# interlinkP1A.net
KiCad netlist of a schematic drawn in Altium Designer
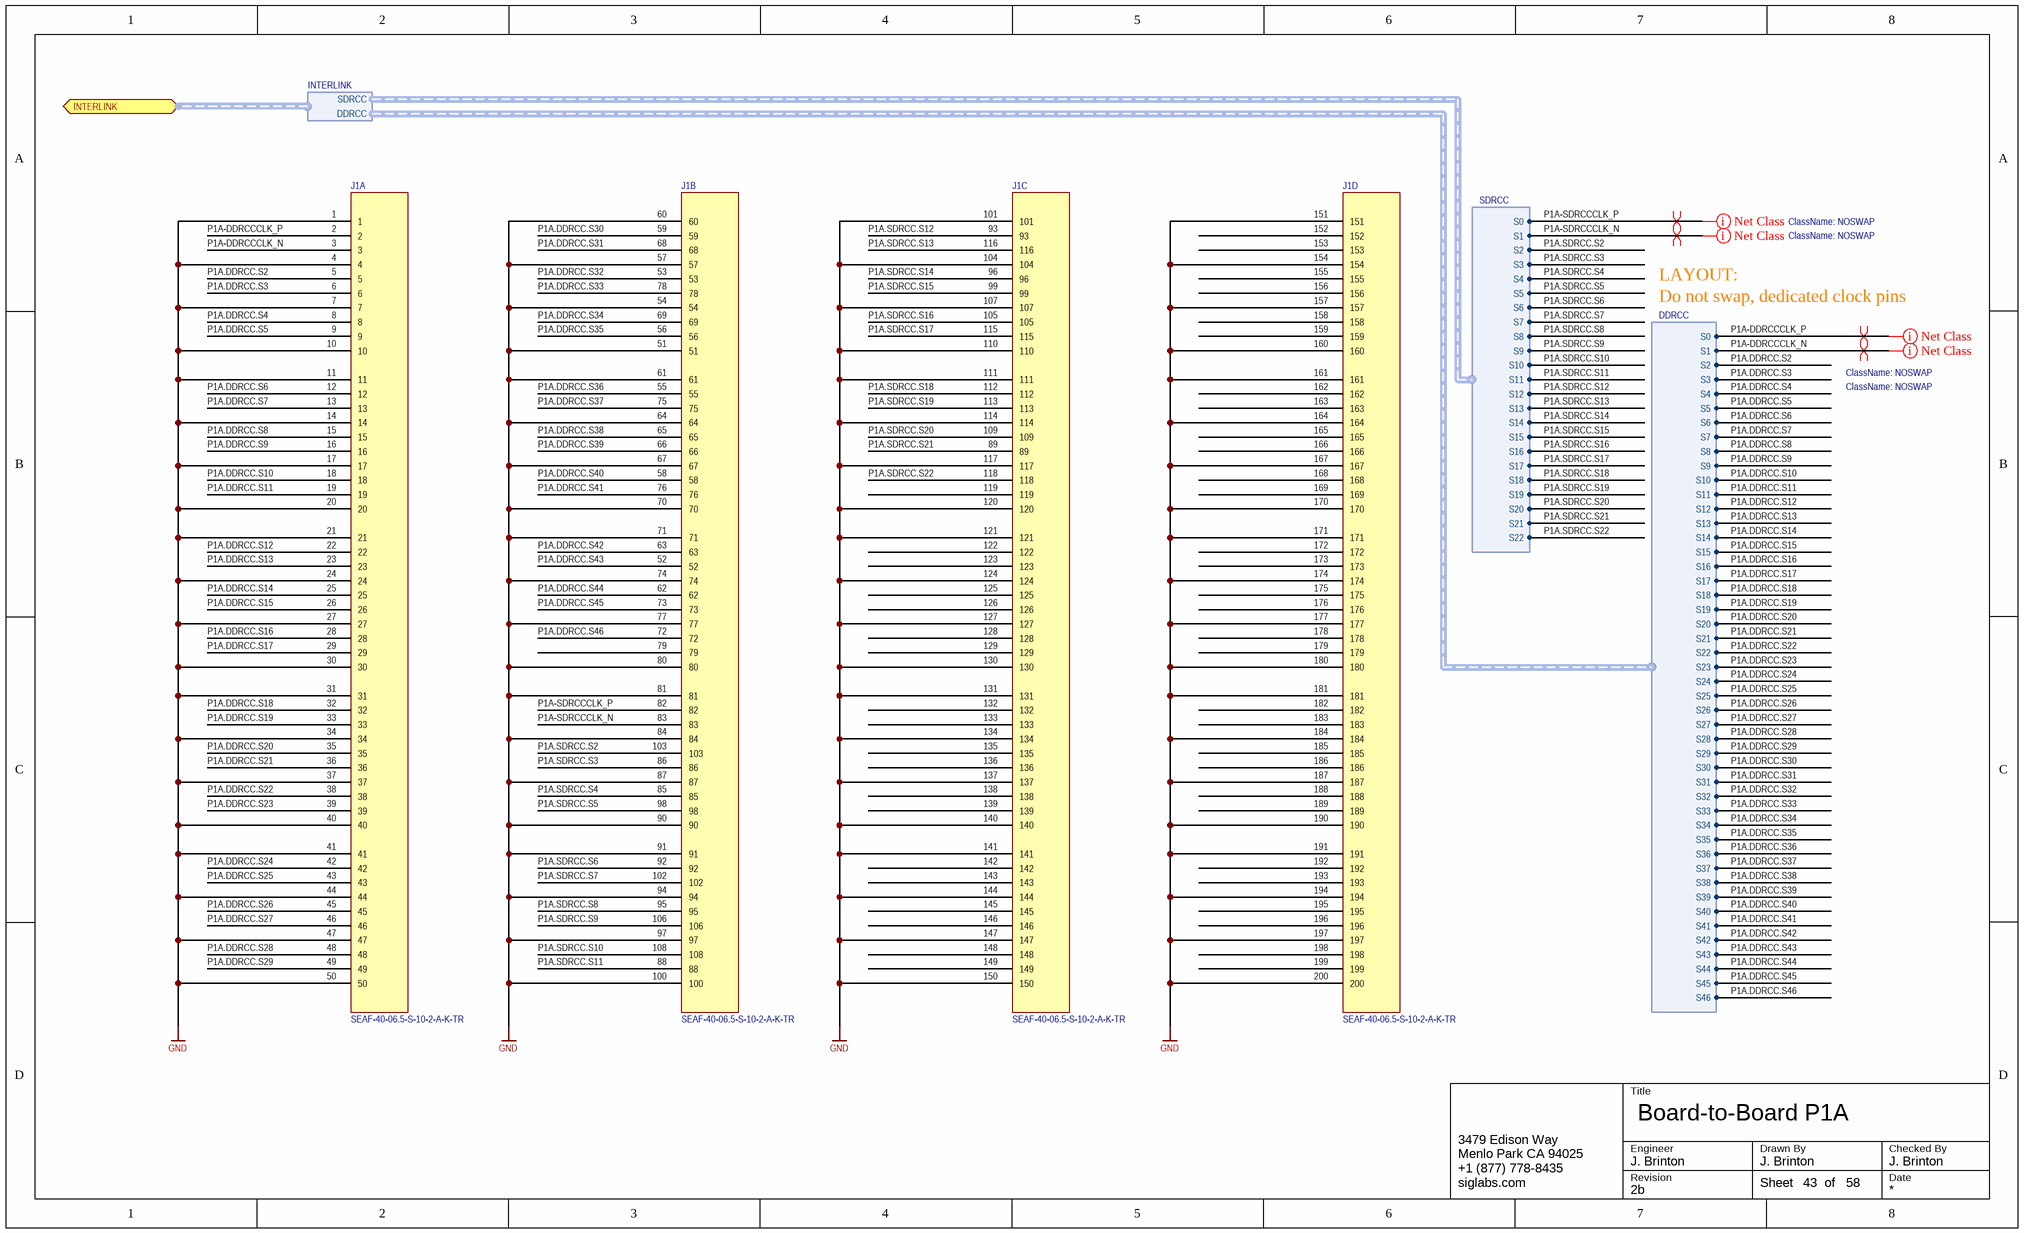
[diagram p0: interlinkP1A.SchDoc]

(export (version "E")
  (design (tool "Eeschema 10.0.6"))
  (components
    (comp (ref "J1")
      (value "SEAF-40-06.5-S-10-2-A-K-TR")
      (footprint "samtec:SEAF-40-06.5-S-10-2-A-K-TR")
      (description "Terminal Array Assembly, Surface Mount, 0.050\" Pitch, 400 Pins")
      (fields (field (name "MANUFACTURER") "Samtec"))
      (libsource (lib "") (part "SEAF-40-06.5-S-10-2-A-K-TR_2"))
    )
  )
  (nets
    (net (code "4") (name "/P1A-DDRCCCLK_N") (class "Default")
      (node (ref "J1") (pin "3") (pinfunction "3_3") (pintype "passive"))
    )
    (net (code "5") (name "/P1A-DDRCCCLK_P") (class "Default")
      (node (ref "J1") (pin "2") (pinfunction "2_2") (pintype "passive"))
    )
    (net (code "6") (name "/P1A-SDRCCCLK_N") (class "Default")
      (node (ref "J1") (pin "83") (pinfunction "83_83") (pintype "passive"))
    )
    (net (code "7") (name "/P1A-SDRCCCLK_P") (class "Default")
      (node (ref "J1") (pin "82") (pinfunction "82_82") (pintype "passive"))
    )
    (net (code "8") (name "/P1A.DDRCC.S2") (class "Default")
      (node (ref "J1") (pin "5") (pinfunction "5_5") (pintype "passive"))
    )
    (net (code "9") (name "/P1A.DDRCC.S3") (class "Default")
      (node (ref "J1") (pin "6") (pinfunction "6_6") (pintype "passive"))
    )
    (net (code "10") (name "/P1A.DDRCC.S4") (class "Default")
      (node (ref "J1") (pin "8") (pinfunction "8_8") (pintype "passive"))
    )
    (net (code "11") (name "/P1A.DDRCC.S5") (class "Default")
      (node (ref "J1") (pin "9") (pinfunction "9_9") (pintype "passive"))
    )
    (net (code "12") (name "/P1A.DDRCC.S6") (class "Default")
      (node (ref "J1") (pin "12") (pinfunction "12_12") (pintype "passive"))
    )
    (net (code "13") (name "/P1A.DDRCC.S7") (class "Default")
      (node (ref "J1") (pin "13") (pinfunction "13_13") (pintype "passive"))
    )
    (net (code "14") (name "/P1A.DDRCC.S8") (class "Default")
      (node (ref "J1") (pin "15") (pinfunction "15_15") (pintype "passive"))
    )
    (net (code "15") (name "/P1A.DDRCC.S9") (class "Default")
      (node (ref "J1") (pin "16") (pinfunction "16_16") (pintype "passive"))
    )
    (net (code "16") (name "/P1A.DDRCC.S10") (class "Default")
      (node (ref "J1") (pin "18") (pinfunction "18_18") (pintype "passive"))
    )
    (net (code "17") (name "/P1A.DDRCC.S11") (class "Default")
      (node (ref "J1") (pin "19") (pinfunction "19_19") (pintype "passive"))
    )
    (net (code "18") (name "/P1A.DDRCC.S12") (class "Default")
      (node (ref "J1") (pin "22") (pinfunction "22_22") (pintype "passive"))
    )
    (net (code "19") (name "/P1A.DDRCC.S13") (class "Default")
      (node (ref "J1") (pin "23") (pinfunction "23_23") (pintype "passive"))
    )
    (net (code "20") (name "/P1A.DDRCC.S14") (class "Default")
      (node (ref "J1") (pin "25") (pinfunction "25_25") (pintype "passive"))
    )
    (net (code "21") (name "/P1A.DDRCC.S15") (class "Default")
      (node (ref "J1") (pin "26") (pinfunction "26_26") (pintype "passive"))
    )
    (net (code "22") (name "/P1A.DDRCC.S16") (class "Default")
      (node (ref "J1") (pin "28") (pinfunction "28_28") (pintype "passive"))
    )
    (net (code "23") (name "/P1A.DDRCC.S17") (class "Default")
      (node (ref "J1") (pin "29") (pinfunction "29_29") (pintype "passive"))
    )
    (net (code "24") (name "/P1A.DDRCC.S18") (class "Default")
      (node (ref "J1") (pin "32") (pinfunction "32_32") (pintype "passive"))
    )
    (net (code "25") (name "/P1A.DDRCC.S19") (class "Default")
      (node (ref "J1") (pin "33") (pinfunction "33_33") (pintype "passive"))
    )
    (net (code "26") (name "/P1A.DDRCC.S20") (class "Default")
      (node (ref "J1") (pin "35") (pinfunction "35_35") (pintype "passive"))
    )
    (net (code "27") (name "/P1A.DDRCC.S21") (class "Default")
      (node (ref "J1") (pin "36") (pinfunction "36_36") (pintype "passive"))
    )
    (net (code "28") (name "/P1A.DDRCC.S22") (class "Default")
      (node (ref "J1") (pin "38") (pinfunction "38_38") (pintype "passive"))
    )
    (net (code "29") (name "/P1A.DDRCC.S23") (class "Default")
      (node (ref "J1") (pin "39") (pinfunction "39_39") (pintype "passive"))
    )
    (net (code "30") (name "/P1A.DDRCC.S24") (class "Default")
      (node (ref "J1") (pin "42") (pinfunction "42_42") (pintype "passive"))
    )
    (net (code "31") (name "/P1A.DDRCC.S25") (class "Default")
      (node (ref "J1") (pin "43") (pinfunction "43_43") (pintype "passive"))
    )
    (net (code "32") (name "/P1A.DDRCC.S26") (class "Default")
      (node (ref "J1") (pin "45") (pinfunction "45_45") (pintype "passive"))
    )
    (net (code "33") (name "/P1A.DDRCC.S27") (class "Default")
      (node (ref "J1") (pin "46") (pinfunction "46_46") (pintype "passive"))
    )
    (net (code "34") (name "/P1A.DDRCC.S28") (class "Default")
      (node (ref "J1") (pin "48") (pinfunction "48_48") (pintype "passive"))
    )
    (net (code "35") (name "/P1A.DDRCC.S29") (class "Default")
      (node (ref "J1") (pin "49") (pinfunction "49_49") (pintype "passive"))
    )
    (net (code "36") (name "/P1A.DDRCC.S30") (class "Default")
      (node (ref "J1") (pin "59") (pinfunction "59_59") (pintype "passive"))
    )
    (net (code "37") (name "/P1A.DDRCC.S31") (class "Default")
      (node (ref "J1") (pin "68") (pinfunction "68_68") (pintype "passive"))
    )
    (net (code "38") (name "/P1A.DDRCC.S32") (class "Default")
      (node (ref "J1") (pin "53") (pinfunction "53_53") (pintype "passive"))
    )
    (net (code "39") (name "/P1A.DDRCC.S33") (class "Default")
      (node (ref "J1") (pin "78") (pinfunction "78_78") (pintype "passive"))
    )
    (net (code "40") (name "/P1A.DDRCC.S34") (class "Default")
      (node (ref "J1") (pin "69") (pinfunction "69_69") (pintype "passive"))
    )
    (net (code "41") (name "/P1A.DDRCC.S35") (class "Default")
      (node (ref "J1") (pin "56") (pinfunction "56_56") (pintype "passive"))
    )
    (net (code "42") (name "/P1A.DDRCC.S36") (class "Default")
      (node (ref "J1") (pin "55") (pinfunction "55_55") (pintype "passive"))
    )
    (net (code "43") (name "/P1A.DDRCC.S37") (class "Default")
      (node (ref "J1") (pin "75") (pinfunction "75_75") (pintype "passive"))
    )
    (net (code "44") (name "/P1A.DDRCC.S38") (class "Default")
      (node (ref "J1") (pin "65") (pinfunction "65_65") (pintype "passive"))
    )
    (net (code "45") (name "/P1A.DDRCC.S39") (class "Default")
      (node (ref "J1") (pin "66") (pinfunction "66_66") (pintype "passive"))
    )
    (net (code "46") (name "/P1A.DDRCC.S40") (class "Default")
      (node (ref "J1") (pin "58") (pinfunction "58_58") (pintype "passive"))
    )
    (net (code "47") (name "/P1A.DDRCC.S41") (class "Default")
      (node (ref "J1") (pin "76") (pinfunction "76_76") (pintype "passive"))
    )
    (net (code "48") (name "/P1A.DDRCC.S42") (class "Default")
      (node (ref "J1") (pin "63") (pinfunction "63_63") (pintype "passive"))
    )
    (net (code "49") (name "/P1A.DDRCC.S43") (class "Default")
      (node (ref "J1") (pin "52") (pinfunction "52_52") (pintype "passive"))
    )
    (net (code "50") (name "/P1A.DDRCC.S44") (class "Default")
      (node (ref "J1") (pin "62") (pinfunction "62_62") (pintype "passive"))
    )
    (net (code "51") (name "/P1A.DDRCC.S45") (class "Default")
      (node (ref "J1") (pin "73") (pinfunction "73_73") (pintype "passive"))
    )
    (net (code "52") (name "/P1A.DDRCC.S46") (class "Default")
      (node (ref "J1") (pin "72") (pinfunction "72_72") (pintype "passive"))
    )
    (net (code "53") (name "/P1A.SDRCC.S2") (class "Default")
      (node (ref "J1") (pin "103") (pinfunction "103_103") (pintype "passive"))
    )
    (net (code "54") (name "/P1A.SDRCC.S3") (class "Default")
      (node (ref "J1") (pin "86") (pinfunction "86_86") (pintype "passive"))
    )
    (net (code "55") (name "/P1A.SDRCC.S4") (class "Default")
      (node (ref "J1") (pin "85") (pinfunction "85_85") (pintype "passive"))
    )
    (net (code "56") (name "/P1A.SDRCC.S5") (class "Default")
      (node (ref "J1") (pin "98") (pinfunction "98_98") (pintype "passive"))
    )
    (net (code "57") (name "/P1A.SDRCC.S6") (class "Default")
      (node (ref "J1") (pin "92") (pinfunction "92_92") (pintype "passive"))
    )
    (net (code "58") (name "/P1A.SDRCC.S7") (class "Default")
      (node (ref "J1") (pin "102") (pinfunction "102_102") (pintype "passive"))
    )
    (net (code "59") (name "/P1A.SDRCC.S8") (class "Default")
      (node (ref "J1") (pin "95") (pinfunction "95_95") (pintype "passive"))
    )
    (net (code "60") (name "/P1A.SDRCC.S9") (class "Default")
      (node (ref "J1") (pin "106") (pinfunction "106_106") (pintype "passive"))
    )
    (net (code "61") (name "/P1A.SDRCC.S10") (class "Default")
      (node (ref "J1") (pin "108") (pinfunction "108_108") (pintype "passive"))
    )
    (net (code "62") (name "/P1A.SDRCC.S11") (class "Default")
      (node (ref "J1") (pin "88") (pinfunction "88_88") (pintype "passive"))
    )
    (net (code "63") (name "/P1A.SDRCC.S12") (class "Default")
      (node (ref "J1") (pin "93") (pinfunction "93_93") (pintype "passive"))
    )
    (net (code "64") (name "/P1A.SDRCC.S13") (class "Default")
      (node (ref "J1") (pin "116") (pinfunction "116_116") (pintype "passive"))
    )
    (net (code "65") (name "/P1A.SDRCC.S14") (class "Default")
      (node (ref "J1") (pin "96") (pinfunction "96_96") (pintype "passive"))
    )
    (net (code "66") (name "/P1A.SDRCC.S15") (class "Default")
      (node (ref "J1") (pin "99") (pinfunction "99_99") (pintype "passive"))
    )
    (net (code "67") (name "/P1A.SDRCC.S16") (class "Default")
      (node (ref "J1") (pin "105") (pinfunction "105_105") (pintype "passive"))
    )
    (net (code "68") (name "/P1A.SDRCC.S17") (class "Default")
      (node (ref "J1") (pin "115") (pinfunction "115_115") (pintype "passive"))
    )
    (net (code "69") (name "/P1A.SDRCC.S18") (class "Default")
      (node (ref "J1") (pin "112") (pinfunction "112_112") (pintype "passive"))
    )
    (net (code "70") (name "/P1A.SDRCC.S19") (class "Default")
      (node (ref "J1") (pin "113") (pinfunction "113_113") (pintype "passive"))
    )
    (net (code "71") (name "/P1A.SDRCC.S20") (class "Default")
      (node (ref "J1") (pin "109") (pinfunction "109_109") (pintype "passive"))
    )
    (net (code "72") (name "/P1A.SDRCC.S21") (class "Default")
      (node (ref "J1") (pin "89") (pinfunction "89_89") (pintype "passive"))
    )
    (net (code "73") (name "/P1A.SDRCC.S22") (class "Default")
      (node (ref "J1") (pin "118") (pinfunction "118_118") (pintype "passive"))
    )
    (net (code "75") (name "GND") (class "Default")
      (node (ref "J1") (pin "1") (pinfunction "1_1") (pintype "passive"))
      (node (ref "J1") (pin "10") (pinfunction "10_10") (pintype "passive"))
      (node (ref "J1") (pin "100") (pinfunction "100_100") (pintype "passive"))
      (node (ref "J1") (pin "101") (pinfunction "101_101") (pintype "passive"))
      (node (ref "J1") (pin "104") (pinfunction "104_104") (pintype "passive"))
      (node (ref "J1") (pin "107") (pinfunction "107_107") (pintype "passive"))
      (node (ref "J1") (pin "11") (pinfunction "11_11") (pintype "passive"))
      (node (ref "J1") (pin "110") (pinfunction "110_110") (pintype "passive"))
      (node (ref "J1") (pin "111") (pinfunction "111_111") (pintype "passive"))
      (node (ref "J1") (pin "114") (pinfunction "114_114") (pintype "passive"))
      (node (ref "J1") (pin "117") (pinfunction "117_117") (pintype "passive"))
      (node (ref "J1") (pin "120") (pinfunction "120_120") (pintype "passive"))
      (node (ref "J1") (pin "121") (pinfunction "121_121") (pintype "passive"))
      (node (ref "J1") (pin "124") (pinfunction "124_124") (pintype "passive"))
      (node (ref "J1") (pin "127") (pinfunction "127_127") (pintype "passive"))
      (node (ref "J1") (pin "130") (pinfunction "130_130") (pintype "passive"))
      (node (ref "J1") (pin "131") (pinfunction "131_131") (pintype "passive"))
      (node (ref "J1") (pin "134") (pinfunction "134_134") (pintype "passive"))
      (node (ref "J1") (pin "137") (pinfunction "137_137") (pintype "passive"))
      (node (ref "J1") (pin "14") (pinfunction "14_14") (pintype "passive"))
      (node (ref "J1") (pin "140") (pinfunction "140_140") (pintype "passive"))
      (node (ref "J1") (pin "141") (pinfunction "141_141") (pintype "passive"))
      (node (ref "J1") (pin "144") (pinfunction "144_144") (pintype "passive"))
      (node (ref "J1") (pin "147") (pinfunction "147_147") (pintype "passive"))
      (node (ref "J1") (pin "150") (pinfunction "150_150") (pintype "passive"))
      (node (ref "J1") (pin "151") (pinfunction "151_151") (pintype "passive"))
      (node (ref "J1") (pin "154") (pinfunction "154_154") (pintype "passive"))
      (node (ref "J1") (pin "157") (pinfunction "157_157") (pintype "passive"))
      (node (ref "J1") (pin "160") (pinfunction "160_160") (pintype "passive"))
      (node (ref "J1") (pin "161") (pinfunction "161_161") (pintype "passive"))
      (node (ref "J1") (pin "164") (pinfunction "164_164") (pintype "passive"))
      (node (ref "J1") (pin "167") (pinfunction "167_167") (pintype "passive"))
      (node (ref "J1") (pin "17") (pinfunction "17_17") (pintype "passive"))
      (node (ref "J1") (pin "170") (pinfunction "170_170") (pintype "passive"))
      (node (ref "J1") (pin "171") (pinfunction "171_171") (pintype "passive"))
      (node (ref "J1") (pin "174") (pinfunction "174_174") (pintype "passive"))
      (node (ref "J1") (pin "177") (pinfunction "177_177") (pintype "passive"))
      (node (ref "J1") (pin "180") (pinfunction "180_180") (pintype "passive"))
      (node (ref "J1") (pin "181") (pinfunction "181_181") (pintype "passive"))
      (node (ref "J1") (pin "184") (pinfunction "184_184") (pintype "passive"))
      (node (ref "J1") (pin "187") (pinfunction "187_187") (pintype "passive"))
      (node (ref "J1") (pin "190") (pinfunction "190_190") (pintype "passive"))
      (node (ref "J1") (pin "191") (pinfunction "191_191") (pintype "passive"))
      (node (ref "J1") (pin "194") (pinfunction "194_194") (pintype "passive"))
      (node (ref "J1") (pin "197") (pinfunction "197_197") (pintype "passive"))
      (node (ref "J1") (pin "20") (pinfunction "20_20") (pintype "passive"))
      (node (ref "J1") (pin "200") (pinfunction "200_200") (pintype "passive"))
      (node (ref "J1") (pin "21") (pinfunction "21_21") (pintype "passive"))
      (node (ref "J1") (pin "24") (pinfunction "24_24") (pintype "passive"))
      (node (ref "J1") (pin "27") (pinfunction "27_27") (pintype "passive"))
      (node (ref "J1") (pin "30") (pinfunction "30_30") (pintype "passive"))
      (node (ref "J1") (pin "31") (pinfunction "31_31") (pintype "passive"))
      (node (ref "J1") (pin "34") (pinfunction "34_34") (pintype "passive"))
      (node (ref "J1") (pin "37") (pinfunction "37_37") (pintype "passive"))
      (node (ref "J1") (pin "4") (pinfunction "4_4") (pintype "passive"))
      (node (ref "J1") (pin "40") (pinfunction "40_40") (pintype "passive"))
      (node (ref "J1") (pin "41") (pinfunction "41_41") (pintype "passive"))
      (node (ref "J1") (pin "44") (pinfunction "44_44") (pintype "passive"))
      (node (ref "J1") (pin "47") (pinfunction "47_47") (pintype "passive"))
      (node (ref "J1") (pin "50") (pinfunction "50_50") (pintype "passive"))
      (node (ref "J1") (pin "51") (pinfunction "51_51") (pintype "passive"))
      (node (ref "J1") (pin "54") (pinfunction "54_54") (pintype "passive"))
      (node (ref "J1") (pin "57") (pinfunction "57_57") (pintype "passive"))
      (node (ref "J1") (pin "60") (pinfunction "60_60") (pintype "passive"))
      (node (ref "J1") (pin "61") (pinfunction "61_61") (pintype "passive"))
      (node (ref "J1") (pin "64") (pinfunction "64_64") (pintype "passive"))
      (node (ref "J1") (pin "67") (pinfunction "67_67") (pintype "passive"))
      (node (ref "J1") (pin "7") (pinfunction "7_7") (pintype "passive"))
      (node (ref "J1") (pin "70") (pinfunction "70_70") (pintype "passive"))
      (node (ref "J1") (pin "71") (pinfunction "71_71") (pintype "passive"))
      (node (ref "J1") (pin "74") (pinfunction "74_74") (pintype "passive"))
      (node (ref "J1") (pin "77") (pinfunction "77_77") (pintype "passive"))
      (node (ref "J1") (pin "80") (pinfunction "80_80") (pintype "passive"))
      (node (ref "J1") (pin "81") (pinfunction "81_81") (pintype "passive"))
      (node (ref "J1") (pin "84") (pinfunction "84_84") (pintype "passive"))
      (node (ref "J1") (pin "87") (pinfunction "87_87") (pintype "passive"))
      (node (ref "J1") (pin "90") (pinfunction "90_90") (pintype "passive"))
      (node (ref "J1") (pin "91") (pinfunction "91_91") (pintype "passive"))
      (node (ref "J1") (pin "94") (pinfunction "94_94") (pintype "passive"))
      (node (ref "J1") (pin "97") (pinfunction "97_97") (pintype "passive"))
    )
    (net (code "76") (name "unconnected-(J1-Pad79)") (class "Default")
      (node (ref "J1") (pin "79") (pinfunction "79_79") (pintype "passive"))
    )
    (net (code "77") (name "unconnected-(J1-Pad119)") (class "Default")
      (node (ref "J1") (pin "119") (pinfunction "119_119") (pintype "passive"))
    )
    (net (code "78") (name "unconnected-(J1-Pad122)") (class "Default")
      (node (ref "J1") (pin "122") (pinfunction "122_122") (pintype "passive"))
    )
    (net (code "79") (name "unconnected-(J1-Pad123)") (class "Default")
      (node (ref "J1") (pin "123") (pinfunction "123_123") (pintype "passive"))
    )
    (net (code "80") (name "unconnected-(J1-Pad125)") (class "Default")
      (node (ref "J1") (pin "125") (pinfunction "125_125") (pintype "passive"))
    )
    (net (code "81") (name "unconnected-(J1-Pad126)") (class "Default")
      (node (ref "J1") (pin "126") (pinfunction "126_126") (pintype "passive"))
    )
    (net (code "82") (name "unconnected-(J1-Pad128)") (class "Default")
      (node (ref "J1") (pin "128") (pinfunction "128_128") (pintype "passive"))
    )
    (net (code "83") (name "unconnected-(J1-Pad129)") (class "Default")
      (node (ref "J1") (pin "129") (pinfunction "129_129") (pintype "passive"))
    )
    (net (code "84") (name "unconnected-(J1-Pad132)") (class "Default")
      (node (ref "J1") (pin "132") (pinfunction "132_132") (pintype "passive"))
    )
    (net (code "85") (name "unconnected-(J1-Pad133)") (class "Default")
      (node (ref "J1") (pin "133") (pinfunction "133_133") (pintype "passive"))
    )
    (net (code "86") (name "unconnected-(J1-Pad135)") (class "Default")
      (node (ref "J1") (pin "135") (pinfunction "135_135") (pintype "passive"))
    )
    (net (code "87") (name "unconnected-(J1-Pad136)") (class "Default")
      (node (ref "J1") (pin "136") (pinfunction "136_136") (pintype "passive"))
    )
    (net (code "88") (name "unconnected-(J1-Pad138)") (class "Default")
      (node (ref "J1") (pin "138") (pinfunction "138_138") (pintype "passive"))
    )
    (net (code "89") (name "unconnected-(J1-Pad139)") (class "Default")
      (node (ref "J1") (pin "139") (pinfunction "139_139") (pintype "passive"))
    )
    (net (code "90") (name "unconnected-(J1-Pad142)") (class "Default")
      (node (ref "J1") (pin "142") (pinfunction "142_142") (pintype "passive"))
    )
    (net (code "91") (name "unconnected-(J1-Pad143)") (class "Default")
      (node (ref "J1") (pin "143") (pinfunction "143_143") (pintype "passive"))
    )
    (net (code "92") (name "unconnected-(J1-Pad145)") (class "Default")
      (node (ref "J1") (pin "145") (pinfunction "145_145") (pintype "passive"))
    )
    (net (code "93") (name "unconnected-(J1-Pad146)") (class "Default")
      (node (ref "J1") (pin "146") (pinfunction "146_146") (pintype "passive"))
    )
    (net (code "94") (name "unconnected-(J1-Pad148)") (class "Default")
      (node (ref "J1") (pin "148") (pinfunction "148_148") (pintype "passive"))
    )
    (net (code "95") (name "unconnected-(J1-Pad149)") (class "Default")
      (node (ref "J1") (pin "149") (pinfunction "149_149") (pintype "passive"))
    )
    (net (code "96") (name "unconnected-(J1-Pad152)") (class "Default")
      (node (ref "J1") (pin "152") (pinfunction "152_152") (pintype "passive"))
    )
    (net (code "97") (name "unconnected-(J1-Pad153)") (class "Default")
      (node (ref "J1") (pin "153") (pinfunction "153_153") (pintype "passive"))
    )
    (net (code "98") (name "unconnected-(J1-Pad155)") (class "Default")
      (node (ref "J1") (pin "155") (pinfunction "155_155") (pintype "passive"))
    )
    (net (code "99") (name "unconnected-(J1-Pad156)") (class "Default")
      (node (ref "J1") (pin "156") (pinfunction "156_156") (pintype "passive"))
    )
    (net (code "100") (name "unconnected-(J1-Pad158)") (class "Default")
      (node (ref "J1") (pin "158") (pinfunction "158_158") (pintype "passive"))
    )
    (net (code "101") (name "unconnected-(J1-Pad159)") (class "Default")
      (node (ref "J1") (pin "159") (pinfunction "159_159") (pintype "passive"))
    )
    (net (code "102") (name "unconnected-(J1-Pad162)") (class "Default")
      (node (ref "J1") (pin "162") (pinfunction "162_162") (pintype "passive"))
    )
    (net (code "103") (name "unconnected-(J1-Pad163)") (class "Default")
      (node (ref "J1") (pin "163") (pinfunction "163_163") (pintype "passive"))
    )
    (net (code "104") (name "unconnected-(J1-Pad165)") (class "Default")
      (node (ref "J1") (pin "165") (pinfunction "165_165") (pintype "passive"))
    )
    (net (code "105") (name "unconnected-(J1-Pad166)") (class "Default")
      (node (ref "J1") (pin "166") (pinfunction "166_166") (pintype "passive"))
    )
    (net (code "106") (name "unconnected-(J1-Pad168)") (class "Default")
      (node (ref "J1") (pin "168") (pinfunction "168_168") (pintype "passive"))
    )
    (net (code "107") (name "unconnected-(J1-Pad169)") (class "Default")
      (node (ref "J1") (pin "169") (pinfunction "169_169") (pintype "passive"))
    )
    (net (code "108") (name "unconnected-(J1-Pad172)") (class "Default")
      (node (ref "J1") (pin "172") (pinfunction "172_172") (pintype "passive"))
    )
    (net (code "109") (name "unconnected-(J1-Pad173)") (class "Default")
      (node (ref "J1") (pin "173") (pinfunction "173_173") (pintype "passive"))
    )
    (net (code "110") (name "unconnected-(J1-Pad175)") (class "Default")
      (node (ref "J1") (pin "175") (pinfunction "175_175") (pintype "passive"))
    )
    (net (code "111") (name "unconnected-(J1-Pad176)") (class "Default")
      (node (ref "J1") (pin "176") (pinfunction "176_176") (pintype "passive"))
    )
    (net (code "112") (name "unconnected-(J1-Pad178)") (class "Default")
      (node (ref "J1") (pin "178") (pinfunction "178_178") (pintype "passive"))
    )
    (net (code "113") (name "unconnected-(J1-Pad179)") (class "Default")
      (node (ref "J1") (pin "179") (pinfunction "179_179") (pintype "passive"))
    )
    (net (code "114") (name "unconnected-(J1-Pad182)") (class "Default")
      (node (ref "J1") (pin "182") (pinfunction "182_182") (pintype "passive"))
    )
    (net (code "115") (name "unconnected-(J1-Pad183)") (class "Default")
      (node (ref "J1") (pin "183") (pinfunction "183_183") (pintype "passive"))
    )
    (net (code "116") (name "unconnected-(J1-Pad185)") (class "Default")
      (node (ref "J1") (pin "185") (pinfunction "185_185") (pintype "passive"))
    )
    (net (code "117") (name "unconnected-(J1-Pad186)") (class "Default")
      (node (ref "J1") (pin "186") (pinfunction "186_186") (pintype "passive"))
    )
    (net (code "118") (name "unconnected-(J1-Pad188)") (class "Default")
      (node (ref "J1") (pin "188") (pinfunction "188_188") (pintype "passive"))
    )
    (net (code "119") (name "unconnected-(J1-Pad189)") (class "Default")
      (node (ref "J1") (pin "189") (pinfunction "189_189") (pintype "passive"))
    )
    (net (code "120") (name "unconnected-(J1-Pad192)") (class "Default")
      (node (ref "J1") (pin "192") (pinfunction "192_192") (pintype "passive"))
    )
    (net (code "121") (name "unconnected-(J1-Pad193)") (class "Default")
      (node (ref "J1") (pin "193") (pinfunction "193_193") (pintype "passive"))
    )
    (net (code "122") (name "unconnected-(J1-Pad195)") (class "Default")
      (node (ref "J1") (pin "195") (pinfunction "195_195") (pintype "passive"))
    )
    (net (code "123") (name "unconnected-(J1-Pad196)") (class "Default")
      (node (ref "J1") (pin "196") (pinfunction "196_196") (pintype "passive"))
    )
    (net (code "124") (name "unconnected-(J1-Pad198)") (class "Default")
      (node (ref "J1") (pin "198") (pinfunction "198_198") (pintype "passive"))
    )
    (net (code "125") (name "unconnected-(J1-Pad199)") (class "Default")
      (node (ref "J1") (pin "199") (pinfunction "199_199") (pintype "passive"))
    )
  )
)
